# Sheet2.net
KiCad netlist of a schematic drawn in Altium Designer
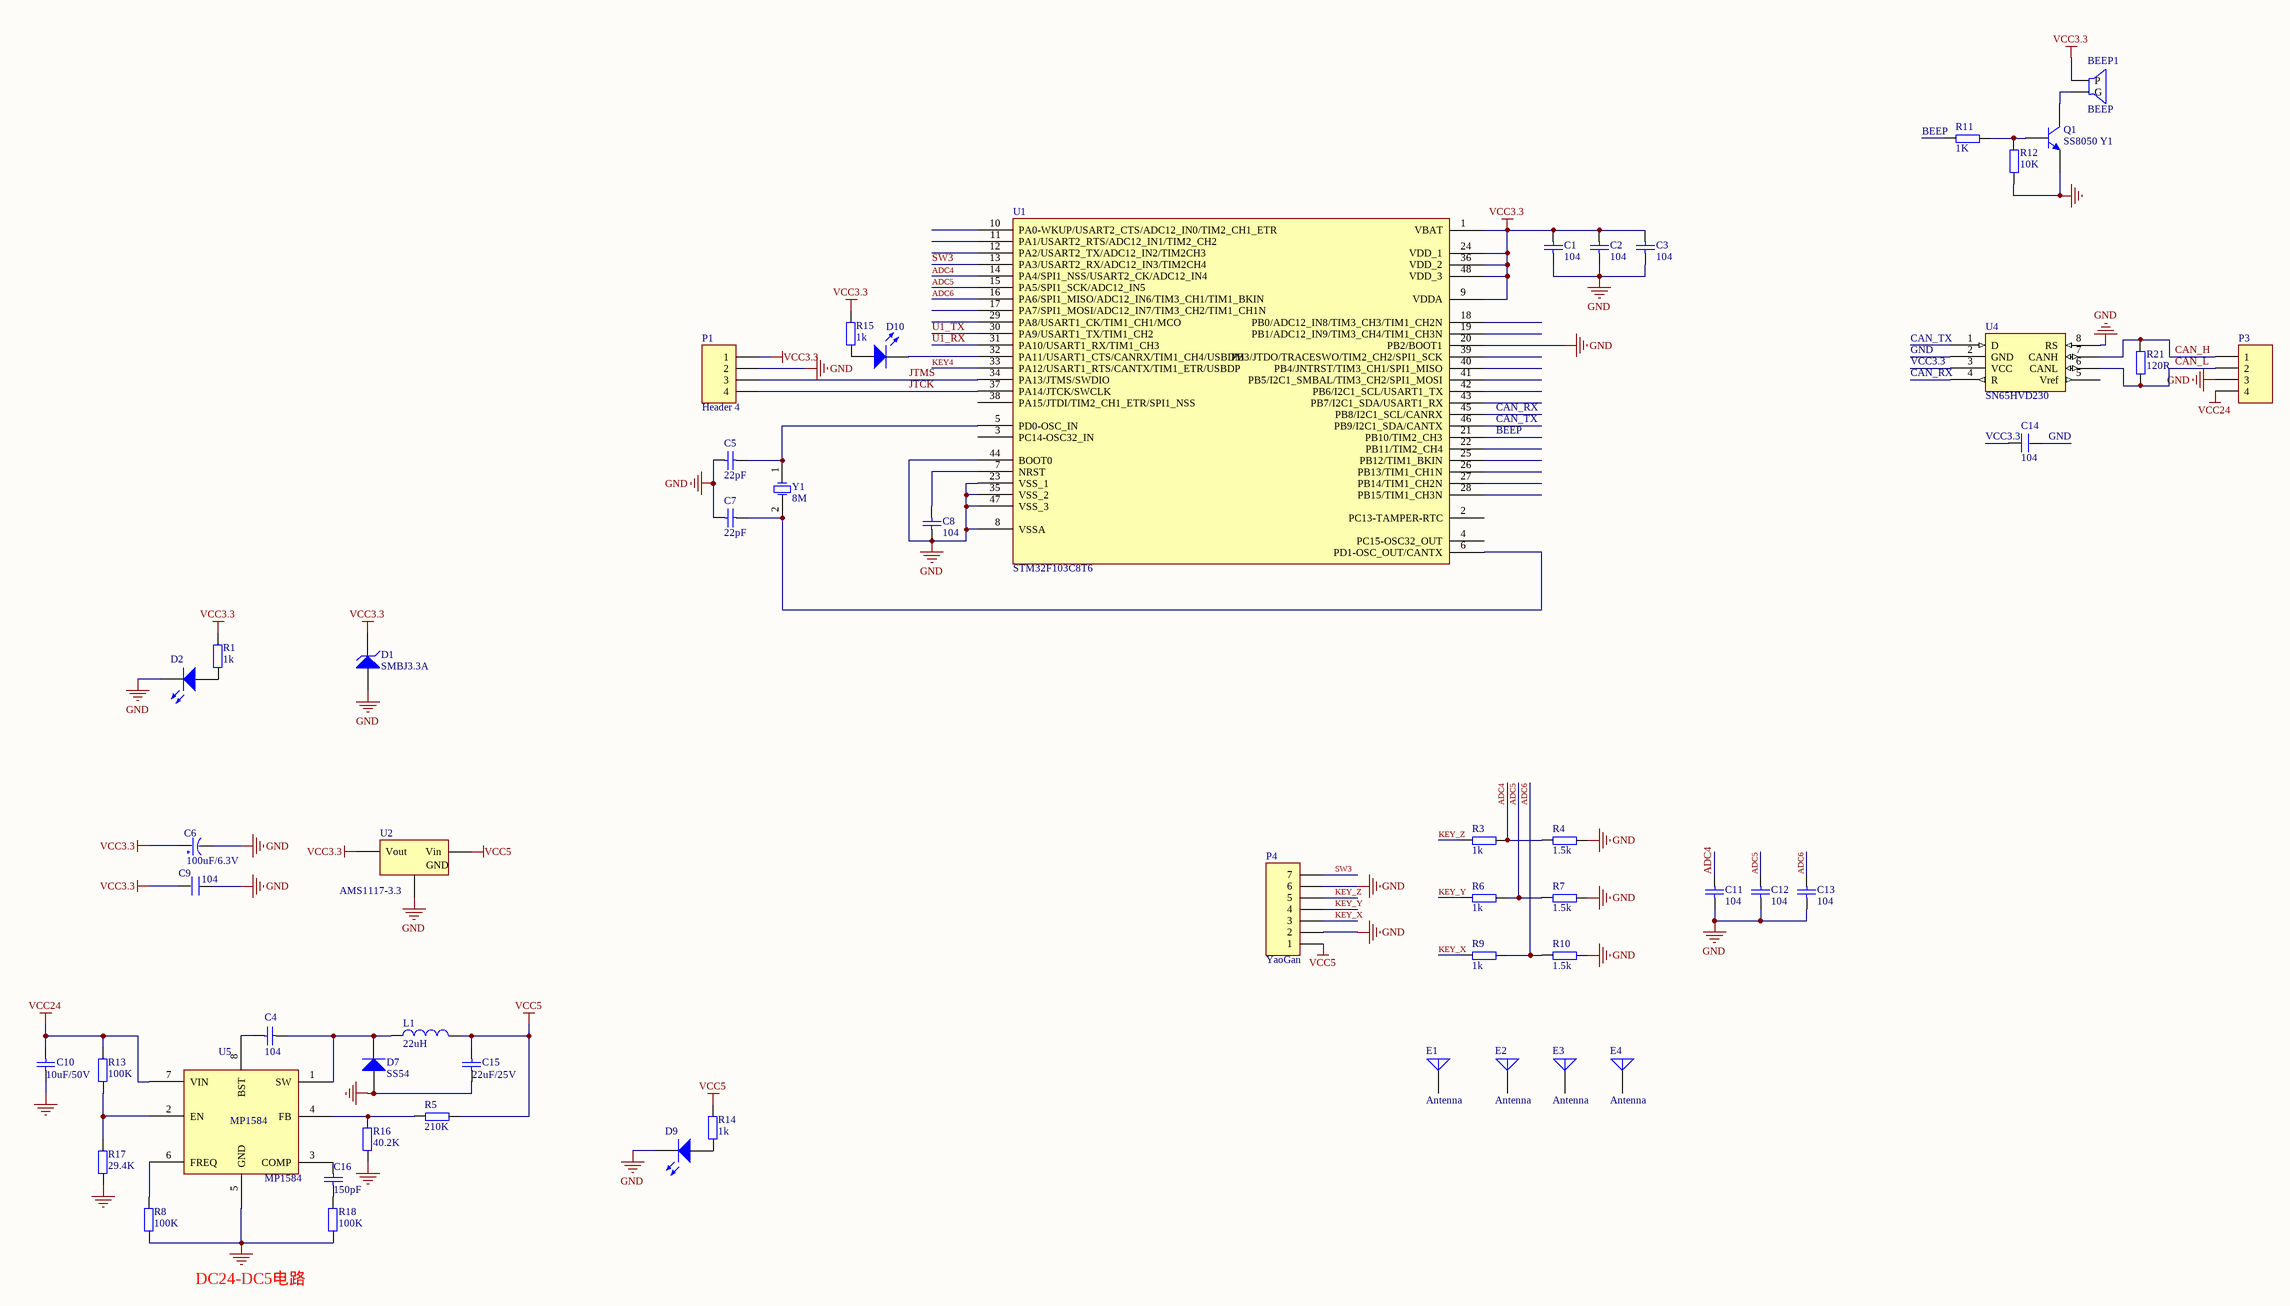
[diagram p0: Sheet2.SchDoc]

(export (version "E")
  (design (tool "Eeschema 10.0.6"))
  (components
    (comp (ref "BEEP1") (value "BEEP") (footprint "BELL-5") (libsource (lib "WarShip V3_SCH") (part "BEEP")))
    (comp (ref "C1")
      (value "104")
      (footprint "0805_C")
      (description "Capacitor")
      (fields (field (name "PUBLISHER") "Altium Limited"))
      (libsource (lib "Miscellaneous Devices") (part "Cap"))
    )
    (comp (ref "C2")
      (value "104")
      (footprint "0805_C")
      (description "Capacitor")
      (fields (field (name "PUBLISHER") "Altium Limited"))
      (libsource (lib "Miscellaneous Devices") (part "Cap"))
    )
    (comp (ref "C3")
      (value "104")
      (footprint "0805_C")
      (description "Capacitor")
      (fields (field (name "PUBLISHER") "Altium Limited"))
      (libsource (lib "Miscellaneous Devices") (part "Cap"))
    )
    (comp (ref "C4")
      (value "104")
      (footprint "0603_C")
      (description "Capacitor (Semiconductor SIM Model)")
      (fields (field (name "PUBLISHER") "Altium Limited"))
      (libsource (lib "Miscellaneous Devices") (part "Cap Semi"))
    )
    (comp (ref "C5")
      (value "22pF")
      (footprint "0805_C")
      (description "Capacitor")
      (fields (field (name "PUBLISHER") "Altium Limited"))
      (libsource (lib "Miscellaneous Devices") (part "Cap"))
    )
    (comp (ref "C6")
      (value "100uF/6.3V")
      (footprint "CASE-B_3528")
      (libsource (lib "WarShip V3_SCH") (part "CAP"))
    )
    (comp (ref "C7")
      (value "22pF")
      (footprint "0805_C")
      (description "Capacitor")
      (fields (field (name "PUBLISHER") "Altium Limited"))
      (libsource (lib "Miscellaneous Devices") (part "Cap"))
    )
    (comp (ref "C8")
      (value "104")
      (footprint "0805_C")
      (description "Capacitor")
      (fields (field (name "PUBLISHER") "Altium Limited"))
      (libsource (lib "Miscellaneous Devices") (part "Cap"))
    )
    (comp (ref "C9") (value "104") (footprint "0805_C") (libsource (lib "WarShip V3_SCH") (part "C")))
    (comp (ref "C10")
      (value "10uF/50V")
      (footprint "1206_C")
      (description "Capacitor (Semiconductor SIM Model)")
      (fields (field (name "PUBLISHER") "Altium Limited"))
      (libsource (lib "Miscellaneous Devices") (part "Cap Semi"))
    )
    (comp (ref "C11")
      (value "104")
      (footprint "0805_C")
      (description "Capacitor")
      (fields (field (name "PUBLISHER") "Altium Limited"))
      (libsource (lib "Miscellaneous Devices") (part "Cap"))
    )
    (comp (ref "C12")
      (value "104")
      (footprint "0805_C")
      (description "Capacitor")
      (fields (field (name "PUBLISHER") "Altium Limited"))
      (libsource (lib "Miscellaneous Devices") (part "Cap"))
    )
    (comp (ref "C13")
      (value "104")
      (footprint "0805_C")
      (description "Capacitor")
      (fields (field (name "PUBLISHER") "Altium Limited"))
      (libsource (lib "Miscellaneous Devices") (part "Cap"))
    )
    (comp (ref "C14")
      (value "104")
      (footprint "0603_C")
      (libsource (lib "Explorer STM32F407封装库") (part "C_3"))
    )
    (comp (ref "C15")
      (value "22uF/25V")
      (footprint "0805_C")
      (description "Capacitor (Semiconductor SIM Model)")
      (fields (field (name "PUBLISHER") "Altium Limited"))
      (libsource (lib "Miscellaneous Devices") (part "Cap Semi"))
    )
    (comp (ref "C16")
      (value "150pF")
      (footprint "0603_C")
      (description "Capacitor (Semiconductor SIM Model)")
      (fields (field (name "PUBLISHER") "Altium Limited"))
      (libsource (lib "Miscellaneous Devices") (part "Cap Semi"))
    )
    (comp (ref "D1")
      (value "SMBJ3.3A")
      (footprint "SMB(DO-214AA)_S1")
      (description "Zener Diode")
      (fields (field (name "PUBLISHER") "Altium Limited"))
      (libsource (lib "Miscellaneous Devices") (part "D Zener"))
    )
    (comp (ref "D2")
      (value "LED0")
      (footprint "LC-0805_LED_S1")
      (description "Typical INFRARED GaAs LED")
      (fields (field (name "PUBLISHER") "Altium Limited"))
      (libsource (lib "继电器板_1") (part "LED0"))
    )
    (comp (ref "D7")
      (value "SS54")
      (footprint "SMA(DO-214AC)_S1")
      (description "二极管")
      (libsource (lib "Miscellaneous Devices LC") (part "SMA(DO-214AC) SS54"))
    )
    (comp (ref "D9")
      (value "LED0")
      (footprint "LC-0805_LED_S1")
      (description "Typical INFRARED GaAs LED")
      (fields (field (name "PUBLISHER") "Altium Limited"))
      (libsource (lib "继电器板_1") (part "LED0"))
    )
    (comp (ref "D10")
      (value "LED0")
      (footprint "LC-0805_LED_S1")
      (description "Typical INFRARED GaAs LED")
      (fields (field (name "PUBLISHER") "Altium Limited"))
      (libsource (lib "继电器板_1") (part "LED0"))
    )
    (comp (ref "E1")
      (value "Antenna")
      (footprint "定位孔 Φ3.2")
      (description "Generic Antenna")
      (fields (field (name "PUBLISHER") "Altium Limited"))
      (libsource (lib "Miscellaneous Devices") (part "Antenna"))
    )
    (comp (ref "E2")
      (value "Antenna")
      (footprint "定位孔 Φ3.2")
      (description "Generic Antenna")
      (fields (field (name "PUBLISHER") "Altium Limited"))
      (libsource (lib "Miscellaneous Devices") (part "Antenna"))
    )
    (comp (ref "E3")
      (value "Antenna")
      (footprint "定位孔 Φ3.2")
      (description "Generic Antenna")
      (fields (field (name "PUBLISHER") "Altium Limited"))
      (libsource (lib "Miscellaneous Devices") (part "Antenna"))
    )
    (comp (ref "E4")
      (value "Antenna")
      (footprint "定位孔 Φ3.2")
      (description "Generic Antenna")
      (fields (field (name "PUBLISHER") "Altium Limited"))
      (libsource (lib "Miscellaneous Devices") (part "Antenna"))
    )
    (comp (ref "L1")
      (value "22uH")
      (footprint "L-7*7*4mm-S")
      (description "Inductor")
      (fields (field (name "PUBLISHER") "Altium Limited"))
      (libsource (lib "Miscellaneous Devices") (part "Inductor"))
    )
    (comp (ref "P1")
      (value "Header 4")
      (footprint "IDE4")
      (description "Header, 4-Pin")
      (fields (field (name "PUBLISHER") "Altium Limited"))
      (libsource (lib "Miscellaneous Connectors") (part "Header 4"))
    )
    (comp (ref "P3")
      (value "~")
      (footprint "DZ-4-3.5")
      (description "Header, 4-Pin")
      (fields (field (name "PUBLISHER") "Altium Limited"))
      (libsource (lib "") (part "Header 4_1"))
    )
    (comp (ref "P4")
      (value "YaoGan")
      (footprint "XH7")
      (description "Header, 7-Pin")
      (fields (field (name "PUBLISHER") "Altium Limited"))
      (libsource (lib "Miscellaneous Connectors") (part "Header 7"))
    )
    (comp (ref "Q1")
      (value "SS8050 Y1")
      (footprint "SOT-23(SOT-23-3)")
      (description "三极管")
      (libsource (lib "Miscellaneous Devices LC") (part "SOT-23 SS8050 Y1"))
    )
    (comp (ref "R1") (value "1k") (footprint "0603_R") (libsource (lib "Explorer STM32F407封装库") (part "R_2")))
    (comp (ref "R3") (value "1k") (footprint "0603_R") (libsource (lib "Explorer STM32F407封装库") (part "R_2")))
    (comp (ref "R4")
      (value "1.5k")
      (footprint "0603_R")
      (libsource (lib "Explorer STM32F407封装库") (part "R_2"))
    )
    (comp (ref "R5")
      (value "210K")
      (footprint "0603_R")
      (libsource (lib "Explorer STM32F407封装库") (part "R_2"))
    )
    (comp (ref "R6") (value "1k") (footprint "0603_R") (libsource (lib "Explorer STM32F407封装库") (part "R_2")))
    (comp (ref "R7")
      (value "1.5k")
      (footprint "0603_R")
      (libsource (lib "Explorer STM32F407封装库") (part "R_2"))
    )
    (comp (ref "R8")
      (value "100K")
      (footprint "0603_R")
      (libsource (lib "Explorer STM32F407封装库") (part "R_2"))
    )
    (comp (ref "R9") (value "1k") (footprint "0603_R") (libsource (lib "Explorer STM32F407封装库") (part "R_2")))
    (comp (ref "R10")
      (value "1.5k")
      (footprint "0603_R")
      (libsource (lib "Explorer STM32F407封装库") (part "R_2"))
    )
    (comp (ref "R11") (value "1K") (footprint "0805_R") (libsource (lib "WarShip V3_SCH") (part "R")))
    (comp (ref "R12") (value "10K") (footprint "0805_R") (libsource (lib "WarShip V3_SCH") (part "R")))
    (comp (ref "R13")
      (value "100K")
      (footprint "0603_R")
      (libsource (lib "Explorer STM32F407封装库") (part "R_2"))
    )
    (comp (ref "R14")
      (value "1k")
      (footprint "0603_R")
      (libsource (lib "Explorer STM32F407封装库") (part "R_2"))
    )
    (comp (ref "R15")
      (value "1k")
      (footprint "0603_R")
      (libsource (lib "Explorer STM32F407封装库") (part "R_2"))
    )
    (comp (ref "R16")
      (value "40.2K")
      (footprint "0603_R")
      (libsource (lib "Explorer STM32F407封装库") (part "R_2"))
    )
    (comp (ref "R17")
      (value "29.4K")
      (footprint "0603_R")
      (libsource (lib "Explorer STM32F407封装库") (part "R_2"))
    )
    (comp (ref "R18")
      (value "100K")
      (footprint "0603_R")
      (libsource (lib "Explorer STM32F407封装库") (part "R_2"))
    )
    (comp (ref "R21")
      (value "120R")
      (footprint "0603_R")
      (libsource (lib "Explorer STM32F407封装库") (part "R_2"))
    )
    (comp (ref "U1")
      (value "STM32F103C8T6")
      (footprint "LQFP-48_7x7x05P")
      (libsource (lib "Schlib1") (part "stm32f103v8t6"))
    )
    (comp (ref "U2")
      (value "AMS1117-3.3")
      (footprint "SOT-223")
      (description "低压差线性稳压(LDO)")
      (libsource (lib "Miscellaneous Devices LC") (part "SOT-223 AMS1117-3.3"))
    )
    (comp (ref "U4")
      (value "SN65HVD230")
      (footprint "LC-SOIC-8_150mil")
      (libsource (lib "Explorer STM32F407封装库") (part "SN65HVD230D"))
    )
    (comp (ref "U5")
      (value "MP1584")
      (footprint "LC-SOIC-8_EP_150MIL")
      (libsource (lib "磁导航") (part "MP1584EN"))
    )
    (comp (ref "Y1")
      (value "8M")
      (footprint "XTAL_US")
      (description "Crystal Oscillator")
      (fields (field (name "PUBLISHER") "Altium Limited"))
      (libsource (lib "Miscellaneous Devices") (part "XTAL"))
    )
  )
  (nets
    (net (code "1") (name "/ADC4") (class "Default")
      (node (ref "C11") (pin "2") (pinfunction "2_2") (pintype "passive"))
      (node (ref "R3") (pin "2") (pintype "passive"))
      (node (ref "R4") (pin "1") (pintype "passive"))
      (node (ref "U1") (pin "14") (pinfunction "PA4/SPI1_NSS/USART2_CK/ADC12_IN4_14") (pintype "passive"))
    )
    (net (code "2") (name "/ADC5") (class "Default")
      (node (ref "C12") (pin "1") (pinfunction "1_1") (pintype "passive"))
      (node (ref "R6") (pin "2") (pintype "passive"))
      (node (ref "R7") (pin "1") (pintype "passive"))
      (node (ref "U1") (pin "15") (pinfunction "PA5/SPI1_SCK/ADC12_IN5_15") (pintype "passive"))
    )
    (net (code "3") (name "/ADC6") (class "Default")
      (node (ref "C13") (pin "1") (pinfunction "1_1") (pintype "passive"))
      (node (ref "R10") (pin "1") (pintype "passive"))
      (node (ref "R9") (pin "2") (pintype "passive"))
      (node (ref "U1") (pin "16") (pinfunction "PA6/SPI1_MISO/ADC12_IN6/TIM3_CH1/TIM1_BKIN_16") (pintype "passive"))
    )
    (net (code "4") (name "/BEEP") (class "Default")
      (node (ref "R11") (pin "1") (pintype "passive"))
      (node (ref "U1") (pin "21") (pinfunction "PB10/TIM2_CH3_21") (pintype "passive"))
    )
    (net (code "5") (name "/CAN_H") (class "Default")
      (node (ref "P3") (pin "1") (pinfunction "1_1") (pintype "passive"))
      (node (ref "R21") (pin "2") (pintype "passive"))
      (node (ref "U4") (pin "7") (pinfunction "CANH_7") (pintype "bidirectional"))
    )
    (net (code "6") (name "/CAN_L") (class "Default")
      (node (ref "P3") (pin "2") (pinfunction "2_2") (pintype "passive"))
      (node (ref "R21") (pin "1") (pintype "passive"))
      (node (ref "U4") (pin "6") (pinfunction "CANL_6") (pintype "bidirectional"))
    )
    (net (code "7") (name "/CAN_RX") (class "Default")
      (node (ref "U1") (pin "45") (pinfunction "PB8/I2C1_SCL/CANRX_45") (pintype "passive"))
      (node (ref "U4") (pin "4") (pinfunction "R_4") (pintype "output"))
    )
    (net (code "8") (name "/CAN_TX") (class "Default")
      (node (ref "U1") (pin "46") (pinfunction "PB9/I2C1_SDA/CANTX_46") (pintype "passive"))
      (node (ref "U4") (pin "1") (pinfunction "D_1") (pintype "input"))
    )
    (net (code "9") (name "/JTCK") (class "Default")
      (node (ref "P1") (pin "4") (pinfunction "4_4") (pintype "passive"))
      (node (ref "U1") (pin "37") (pinfunction "PA14/JTCK/SWCLK_37") (pintype "passive"))
    )
    (net (code "10") (name "/JTMS") (class "Default")
      (node (ref "P1") (pin "3") (pinfunction "3_3") (pintype "passive"))
      (node (ref "U1") (pin "34") (pinfunction "PA13/JTMS/SWDIO_34") (pintype "passive"))
    )
    (net (code "11") (name "/KEY4") (class "Default")
      (node (ref "U1") (pin "33") (pinfunction "PA12/USART1_RTS/CANTX/TIM1_ETR/USBDP_33") (pintype "passive"))
    )
    (net (code "12") (name "/KEY_X") (class "Default")
      (node (ref "P4") (pin "3") (pinfunction "3_3") (pintype "passive"))
      (node (ref "R9") (pin "1") (pintype "passive"))
    )
    (net (code "13") (name "/KEY_Y") (class "Default")
      (node (ref "P4") (pin "4") (pinfunction "4_4") (pintype "passive"))
      (node (ref "R6") (pin "1") (pintype "passive"))
    )
    (net (code "14") (name "/KEY_Z") (class "Default")
      (node (ref "P4") (pin "5") (pinfunction "5_5") (pintype "passive"))
      (node (ref "R3") (pin "1") (pintype "passive"))
    )
    (net (code "15") (name "/SW3") (class "Default")
      (node (ref "P4") (pin "7") (pinfunction "7_7") (pintype "passive"))
      (node (ref "U1") (pin "13") (pinfunction "PA3/USART2_RX/ADC12_IN3/TIM2CH4_13") (pintype "passive"))
    )
    (net (code "16") (name "/U1_RX") (class "Default")
      (node (ref "U1") (pin "31") (pinfunction "PA10/USART1_RX/TIM1_CH3_31") (pintype "passive"))
    )
    (net (code "17") (name "/U1_TX") (class "Default")
      (node (ref "U1") (pin "30") (pinfunction "PA9/USART1_TX/TIM1_CH2_30") (pintype "passive"))
    )
    (net (code "18") (name "GND") (class "Default")
      (node (ref "C1") (pin "2") (pinfunction "2_2") (pintype "passive"))
      (node (ref "C10") (pin "2") (pinfunction "2_2") (pintype "passive"))
      (node (ref "C11") (pin "1") (pinfunction "1_1") (pintype "passive"))
      (node (ref "C12") (pin "2") (pinfunction "2_2") (pintype "passive"))
      (node (ref "C13") (pin "2") (pinfunction "2_2") (pintype "passive"))
      (node (ref "C14") (pin "2") (pintype "passive"))
      (node (ref "C15") (pin "1") (pinfunction "1_1") (pintype "passive"))
      (node (ref "C2") (pin "2") (pinfunction "2_2") (pintype "passive"))
      (node (ref "C3") (pin "2") (pinfunction "2_2") (pintype "passive"))
      (node (ref "C5") (pin "2") (pinfunction "2_2") (pintype "passive"))
      (node (ref "C6") (pin "2") (pinfunction "GND_2") (pintype "passive"))
      (node (ref "C7") (pin "2") (pinfunction "2_2") (pintype "passive"))
      (node (ref "C8") (pin "2") (pinfunction "2_2") (pintype "passive"))
      (node (ref "C9") (pin "1") (pintype "passive"))
      (node (ref "D1") (pin "1") (pinfunction "A_1") (pintype "passive"))
      (node (ref "D2") (pin "K") (pinfunction "K_K") (pintype "passive"))
      (node (ref "D7") (pin "1") (pinfunction "A_1") (pintype "passive"))
      (node (ref "D9") (pin "K") (pinfunction "K_K") (pintype "passive"))
      (node (ref "P1") (pin "2") (pinfunction "2_2") (pintype "passive"))
      (node (ref "P3") (pin "3") (pinfunction "3_3") (pintype "passive"))
      (node (ref "P4") (pin "2") (pinfunction "2_2") (pintype "passive"))
      (node (ref "P4") (pin "6") (pinfunction "6_6") (pintype "passive"))
      (node (ref "Q1") (pin "2") (pinfunction "E_2") (pintype "passive"))
      (node (ref "R10") (pin "2") (pintype "passive"))
      (node (ref "R12") (pin "1") (pintype "passive"))
      (node (ref "R16") (pin "2") (pintype "passive"))
      (node (ref "R17") (pin "2") (pintype "passive"))
      (node (ref "R18") (pin "2") (pintype "passive"))
      (node (ref "R4") (pin "2") (pintype "passive"))
      (node (ref "R7") (pin "2") (pintype "passive"))
      (node (ref "R8") (pin "2") (pintype "passive"))
      (node (ref "U1") (pin "20") (pinfunction "PB2/BOOT1_20") (pintype "passive"))
      (node (ref "U1") (pin "23") (pinfunction "VSS_1_23") (pintype "passive"))
      (node (ref "U1") (pin "35") (pinfunction "VSS_2_35") (pintype "passive"))
      (node (ref "U1") (pin "44") (pinfunction "BOOT0_44") (pintype "passive"))
      (node (ref "U1") (pin "47") (pinfunction "VSS_3_47") (pintype "passive"))
      (node (ref "U1") (pin "8") (pinfunction "VSSA_8") (pintype "passive"))
      (node (ref "U2") (pin "1") (pinfunction "GND_1") (pintype "passive"))
      (node (ref "U4") (pin "2") (pinfunction "GND_2") (pintype "power_in"))
      (node (ref "U4") (pin "8") (pinfunction "RS_8") (pintype "input"))
      (node (ref "U5") (pin "5") (pinfunction "GND_5") (pintype "passive"))
    )
    (net (code "19") (name "Net-(BEEP1-G)") (class "Default")
      (node (ref "BEEP1") (pin "2") (pinfunction "G_2") (pintype "passive"))
      (node (ref "Q1") (pin "3") (pinfunction "C_3") (pintype "passive"))
    )
    (net (code "20") (name "Net-(C16-Pad1)") (class "Default")
      (node (ref "C16") (pin "1") (pinfunction "1_1") (pintype "passive"))
      (node (ref "R18") (pin "1") (pintype "passive"))
    )
    (net (code "21") (name "Net-(D2-PadA)") (class "Default")
      (node (ref "D2") (pin "A") (pinfunction "A_A") (pintype "passive"))
      (node (ref "R1") (pin "2") (pintype "passive"))
    )
    (net (code "22") (name "Net-(D7-K)") (class "Default")
      (node (ref "C4") (pin "1") (pinfunction "1_1") (pintype "passive"))
      (node (ref "D7") (pin "2") (pinfunction "K_2") (pintype "passive"))
      (node (ref "L1") (pin "1") (pinfunction "1_1") (pintype "passive"))
      (node (ref "U5") (pin "1") (pinfunction "SW_1") (pintype "passive"))
    )
    (net (code "23") (name "Net-(D9-PadA)") (class "Default")
      (node (ref "D9") (pin "A") (pinfunction "A_A") (pintype "passive"))
      (node (ref "R14") (pin "2") (pintype "passive"))
    )
    (net (code "24") (name "Net-(D10-PadA)") (class "Default")
      (node (ref "D10") (pin "A") (pinfunction "A_A") (pintype "passive"))
      (node (ref "R15") (pin "2") (pintype "passive"))
    )
    (net (code "25") (name "Net-(Q1-B)") (class "Default")
      (node (ref "Q1") (pin "1") (pinfunction "B_1") (pintype "passive"))
      (node (ref "R11") (pin "2") (pintype "passive"))
      (node (ref "R12") (pin "2") (pintype "passive"))
    )
    (net (code "26") (name "Net-(U1-NRST)") (class "Default")
      (node (ref "C8") (pin "1") (pinfunction "1_1") (pintype "passive"))
      (node (ref "U1") (pin "7") (pinfunction "NRST_7") (pintype "passive"))
    )
    (net (code "27") (name "Net-(U1-PA11{slash}USART1_CTS{slash}CANRX{slash}TIM1_CH4{slash}USBDM)") (class "Default")
      (node (ref "D10") (pin "K") (pinfunction "K_K") (pintype "passive"))
      (node (ref "U1") (pin "32") (pinfunction "PA11/USART1_CTS/CANRX/TIM1_CH4/USBDM_32") (pintype "passive"))
    )
    (net (code "28") (name "Net-(U1-PD0-OSC_IN)") (class "Default")
      (node (ref "C5") (pin "1") (pinfunction "1_1") (pintype "passive"))
      (node (ref "U1") (pin "5") (pinfunction "PD0-OSC_IN_5") (pintype "passive"))
      (node (ref "Y1") (pin "1") (pinfunction "OSC1_1") (pintype "passive"))
    )
    (net (code "29") (name "Net-(U1-PD1-OSC_OUT{slash}CANTX)") (class "Default")
      (node (ref "C7") (pin "1") (pinfunction "1_1") (pintype "passive"))
      (node (ref "U1") (pin "6") (pinfunction "PD1-OSC_OUT/CANTX_6") (pintype "passive"))
      (node (ref "Y1") (pin "2") (pinfunction "OSC2_2") (pintype "passive"))
    )
    (net (code "30") (name "Net-(U5-BST)") (class "Default")
      (node (ref "C4") (pin "2") (pinfunction "2_2") (pintype "passive"))
      (node (ref "U5") (pin "8") (pinfunction "BST_8") (pintype "passive"))
    )
    (net (code "31") (name "Net-(U5-COMP)") (class "Default")
      (node (ref "C16") (pin "2") (pinfunction "2_2") (pintype "passive"))
      (node (ref "U5") (pin "3") (pinfunction "COMP_3") (pintype "passive"))
    )
    (net (code "32") (name "Net-(U5-EN)") (class "Default")
      (node (ref "R13") (pin "2") (pintype "passive"))
      (node (ref "R17") (pin "1") (pintype "passive"))
      (node (ref "U5") (pin "2") (pinfunction "EN_2") (pintype "passive"))
    )
    (net (code "33") (name "Net-(U5-FB)") (class "Default")
      (node (ref "R16") (pin "1") (pintype "passive"))
      (node (ref "R5") (pin "1") (pintype "passive"))
      (node (ref "U5") (pin "4") (pinfunction "FB_4") (pintype "passive"))
    )
    (net (code "34") (name "Net-(U5-FREQ)") (class "Default")
      (node (ref "R8") (pin "1") (pintype "passive"))
      (node (ref "U5") (pin "6") (pinfunction "FREQ_6") (pintype "passive"))
    )
    (net (code "35") (name "VCC3.3") (class "Default")
      (node (ref "BEEP1") (pin "1") (pinfunction "P_1") (pintype "passive"))
      (node (ref "C1") (pin "1") (pinfunction "1_1") (pintype "passive"))
      (node (ref "C14") (pin "1") (pintype "passive"))
      (node (ref "C2") (pin "1") (pinfunction "1_1") (pintype "passive"))
      (node (ref "C3") (pin "1") (pinfunction "1_1") (pintype "passive"))
      (node (ref "C6") (pin "1") (pinfunction "VCC_1") (pintype "passive"))
      (node (ref "C9") (pin "2") (pintype "passive"))
      (node (ref "D1") (pin "2") (pinfunction "K_2") (pintype "passive"))
      (node (ref "P1") (pin "1") (pinfunction "1_1") (pintype "passive"))
      (node (ref "R1") (pin "1") (pintype "passive"))
      (node (ref "R15") (pin "1") (pintype "passive"))
      (node (ref "U1") (pin "1") (pinfunction "VBAT_1") (pintype "passive"))
      (node (ref "U1") (pin "24") (pinfunction "VDD_1_24") (pintype "passive"))
      (node (ref "U1") (pin "36") (pinfunction "VDD_2_36") (pintype "passive"))
      (node (ref "U1") (pin "48") (pinfunction "VDD_3_48") (pintype "passive"))
      (node (ref "U1") (pin "9") (pinfunction "VDDA_9") (pintype "passive"))
      (node (ref "U2") (pin "2") (pinfunction "Vout_2") (pintype "passive"))
      (node (ref "U4") (pin "3") (pinfunction "VCC_3") (pintype "power_in"))
    )
    (net (code "36") (name "VCC5") (class "Default")
      (node (ref "C15") (pin "2") (pinfunction "2_2") (pintype "passive"))
      (node (ref "L1") (pin "2") (pinfunction "2_2") (pintype "passive"))
      (node (ref "P4") (pin "1") (pinfunction "1_1") (pintype "passive"))
      (node (ref "R14") (pin "1") (pintype "passive"))
      (node (ref "R5") (pin "2") (pintype "passive"))
      (node (ref "U2") (pin "3") (pinfunction "Vin_3") (pintype "passive"))
    )
    (net (code "37") (name "VCC24") (class "Default")
      (node (ref "C10") (pin "1") (pinfunction "1_1") (pintype "passive"))
      (node (ref "P3") (pin "4") (pinfunction "4_4") (pintype "passive"))
      (node (ref "R13") (pin "1") (pintype "passive"))
      (node (ref "U5") (pin "7") (pinfunction "VIN_7") (pintype "passive"))
    )
    (net (code "38") (name "unconnected-(E1-A-Pad1)") (class "Default")
      (node (ref "E1") (pin "1") (pinfunction "A_1") (pintype "passive"))
    )
    (net (code "39") (name "unconnected-(E2-A-Pad1)") (class "Default")
      (node (ref "E2") (pin "1") (pinfunction "A_1") (pintype "passive"))
    )
    (net (code "40") (name "unconnected-(E3-A-Pad1)") (class "Default")
      (node (ref "E3") (pin "1") (pinfunction "A_1") (pintype "passive"))
    )
    (net (code "41") (name "unconnected-(E4-A-Pad1)") (class "Default")
      (node (ref "E4") (pin "1") (pinfunction "A_1") (pintype "passive"))
    )
    (net (code "42") (name "unconnected-(U1-PA0-WKUP{slash}USART2_CTS{slash}ADC12_IN0{slash}TIM2_CH1_ETR-Pad10)") (class "Default")
      (node (ref "U1") (pin "10") (pinfunction "PA0-WKUP/USART2_CTS/ADC12_IN0/TIM2_CH1_ETR_10") (pintype "passive"))
    )
    (net (code "43") (name "unconnected-(U1-PA1{slash}USART2_RTS{slash}ADC12_IN1{slash}TIM2_CH2-Pad11)") (class "Default")
      (node (ref "U1") (pin "11") (pinfunction "PA1/USART2_RTS/ADC12_IN1/TIM2_CH2_11") (pintype "passive"))
    )
    (net (code "44") (name "unconnected-(U1-PA2{slash}USART2_TX{slash}ADC12_IN2{slash}TIM2CH3-Pad12)") (class "Default")
      (node (ref "U1") (pin "12") (pinfunction "PA2/USART2_TX/ADC12_IN2/TIM2CH3_12") (pintype "passive"))
    )
    (net (code "45") (name "unconnected-(U1-PA7{slash}SPI1_MOSI{slash}ADC12_IN7{slash}TIM3_CH2{slash}TIM1_CH1N-Pad17)") (class "Default")
      (node (ref "U1") (pin "17") (pinfunction "PA7/SPI1_MOSI/ADC12_IN7/TIM3_CH2/TIM1_CH1N_17") (pintype "passive"))
    )
    (net (code "46") (name "unconnected-(U1-PA8{slash}USART1_CK{slash}TIM1_CH1{slash}MCO-Pad29)") (class "Default")
      (node (ref "U1") (pin "29") (pinfunction "PA8/USART1_CK/TIM1_CH1/MCO_29") (pintype "passive"))
    )
    (net (code "47") (name "unconnected-(U1-PA15{slash}JTDI{slash}TIM2_CH1_ETR{slash}SPI1_NSS-Pad38)") (class "Default")
      (node (ref "U1") (pin "38") (pinfunction "PA15/JTDI/TIM2_CH1_ETR/SPI1_NSS_38") (pintype "passive"))
    )
    (net (code "48") (name "unconnected-(U1-PB0{slash}ADC12_IN8{slash}TIM3_CH3{slash}TIM1_CH2N-Pad18)") (class "Default")
      (node (ref "U1") (pin "18") (pinfunction "PB0/ADC12_IN8/TIM3_CH3/TIM1_CH2N_18") (pintype "passive"))
    )
    (net (code "49") (name "unconnected-(U1-PB1{slash}ADC12_IN9{slash}TIM3_CH4{slash}TIM1_CH3N-Pad19)") (class "Default")
      (node (ref "U1") (pin "19") (pinfunction "PB1/ADC12_IN9/TIM3_CH4/TIM1_CH3N_19") (pintype "passive"))
    )
    (net (code "50") (name "unconnected-(U1-PB3{slash}JTDO{slash}TRACESWO{slash}TIM2_CH2{slash}SPI1_SCK-Pad39)") (class "Default")
      (node (ref "U1") (pin "39") (pinfunction "PB3/JTDO/TRACESWO/TIM2_CH2/SPI1_SCK_39") (pintype "passive"))
    )
    (net (code "51") (name "unconnected-(U1-PB4{slash}JNTRST{slash}TIM3_CH1{slash}SPI1_MISO-Pad40)") (class "Default")
      (node (ref "U1") (pin "40") (pinfunction "PB4/JNTRST/TIM3_CH1/SPI1_MISO_40") (pintype "passive"))
    )
    (net (code "52") (name "unconnected-(U1-PB5{slash}I2C1_SMBAL{slash}TIM3_CH2{slash}SPI1_MOSI-Pad41)") (class "Default")
      (node (ref "U1") (pin "41") (pinfunction "PB5/I2C1_SMBAL/TIM3_CH2/SPI1_MOSI_41") (pintype "passive"))
    )
    (net (code "53") (name "unconnected-(U1-PB6{slash}I2C1_SCL{slash}USART1_TX-Pad42)") (class "Default")
      (node (ref "U1") (pin "42") (pinfunction "PB6/I2C1_SCL/USART1_TX_42") (pintype "passive"))
    )
    (net (code "54") (name "unconnected-(U1-PB7{slash}I2C1_SDA{slash}USART1_RX-Pad43)") (class "Default")
      (node (ref "U1") (pin "43") (pinfunction "PB7/I2C1_SDA/USART1_RX_43") (pintype "passive"))
    )
    (net (code "55") (name "unconnected-(U1-PB11{slash}TIM2_CH4-Pad22)") (class "Default")
      (node (ref "U1") (pin "22") (pinfunction "PB11/TIM2_CH4_22") (pintype "passive"))
    )
    (net (code "56") (name "unconnected-(U1-PB12{slash}TIM1_BKIN-Pad25)") (class "Default")
      (node (ref "U1") (pin "25") (pinfunction "PB12/TIM1_BKIN_25") (pintype "passive"))
    )
    (net (code "57") (name "unconnected-(U1-PB13{slash}TIM1_CH1N-Pad26)") (class "Default")
      (node (ref "U1") (pin "26") (pinfunction "PB13/TIM1_CH1N_26") (pintype "passive"))
    )
    (net (code "58") (name "unconnected-(U1-PB14{slash}TIM1_CH2N-Pad27)") (class "Default")
      (node (ref "U1") (pin "27") (pinfunction "PB14/TIM1_CH2N_27") (pintype "passive"))
    )
    (net (code "59") (name "unconnected-(U1-PB15{slash}TIM1_CH3N-Pad28)") (class "Default")
      (node (ref "U1") (pin "28") (pinfunction "PB15/TIM1_CH3N_28") (pintype "passive"))
    )
    (net (code "60") (name "unconnected-(U1-PC13-TAMPER-RTC-Pad2)") (class "Default")
      (node (ref "U1") (pin "2") (pinfunction "PC13-TAMPER-RTC_2") (pintype "passive"))
    )
    (net (code "61") (name "unconnected-(U1-PC14-OSC32_IN-Pad3)") (class "Default")
      (node (ref "U1") (pin "3") (pinfunction "PC14-OSC32_IN_3") (pintype "passive"))
    )
    (net (code "62") (name "unconnected-(U1-PC15-OSC32_OUT-Pad4)") (class "Default")
      (node (ref "U1") (pin "4") (pinfunction "PC15-OSC32_OUT_4") (pintype "passive"))
    )
    (net (code "63") (name "unconnected-(U4-Vref-Pad5)") (class "Default")
      (node (ref "U4") (pin "5") (pinfunction "Vref_5") (pintype "output"))
    )
  )
)
